# pcm2705_DAC.net
KiCad netlist of a schematic drawn in EAGLE
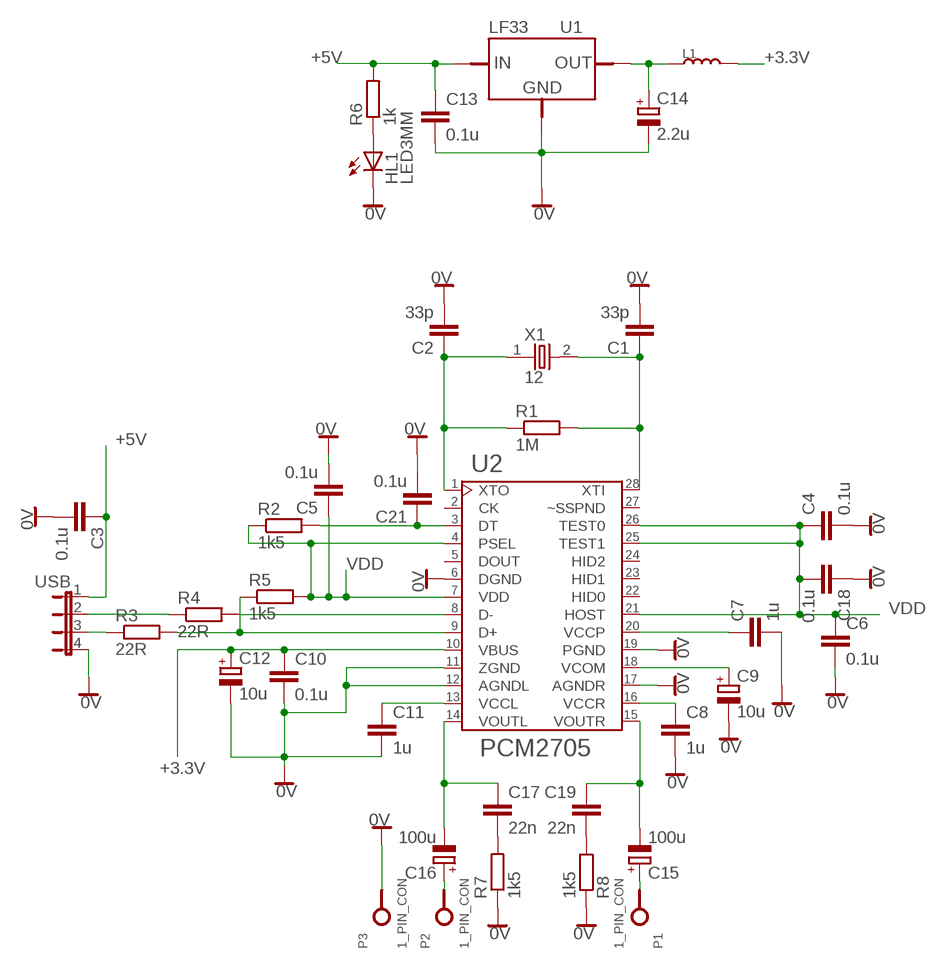
[diagram p0: schematic, sheet 1]

(export (version "E")
  (design (tool "Eeschema 10.0.6"))
  (components
    (comp (ref "C1")
      (value "33p")
      (footprint "eagle-import:C0805D")
      (libsource (lib "eagle-import") (part "C0805"))
    )
    (comp (ref "C2")
      (value "33p")
      (footprint "eagle-import:C0805D")
      (libsource (lib "eagle-import") (part "C0805"))
    )
    (comp (ref "C3")
      (value "0.1u")
      (footprint "eagle-import:C0805D")
      (libsource (lib "eagle-import") (part "C0805"))
    )
    (comp (ref "C4")
      (value "0.1u")
      (footprint "eagle-import:C0805D")
      (libsource (lib "eagle-import") (part "C0805"))
    )
    (comp (ref "C5")
      (value "0.1u")
      (footprint "eagle-import:C0805D")
      (libsource (lib "eagle-import") (part "C0805"))
    )
    (comp (ref "C6")
      (value "0.1u")
      (footprint "eagle-import:C0805D")
      (libsource (lib "eagle-import") (part "C0805"))
    )
    (comp (ref "C7")
      (value "1u")
      (footprint "eagle-import:C0805D")
      (libsource (lib "eagle-import") (part "C0805"))
    )
    (comp (ref "C8")
      (value "1u")
      (footprint "eagle-import:C0805D")
      (libsource (lib "eagle-import") (part "C0805"))
    )
    (comp (ref "C9")
      (value "10u")
      (footprint "eagle-import:C100MILX6X12")
      (libsource (lib "eagle-import") (part "C100MFX25V"))
    )
    (comp (ref "C10")
      (value "0.1u")
      (footprint "eagle-import:C0805D")
      (libsource (lib "eagle-import") (part "C0805"))
    )
    (comp (ref "C11")
      (value "1u")
      (footprint "eagle-import:C0805D")
      (libsource (lib "eagle-import") (part "C0805"))
    )
    (comp (ref "C12")
      (value "10u")
      (footprint "eagle-import:C100MILX6X12")
      (libsource (lib "eagle-import") (part "C100MFX25V"))
    )
    (comp (ref "C13")
      (value "0.1u")
      (footprint "eagle-import:C0805D")
      (libsource (lib "eagle-import") (part "C0805"))
    )
    (comp (ref "C14")
      (value "2.2u")
      (footprint "eagle-import:C100MILX6X12")
      (libsource (lib "eagle-import") (part "C100MFX25V"))
    )
    (comp (ref "C15")
      (value "100u")
      (footprint "eagle-import:C100MILX6X12")
      (libsource (lib "eagle-import") (part "C100MFX25V"))
    )
    (comp (ref "C16")
      (value "100u")
      (footprint "eagle-import:C100MILX6X12")
      (libsource (lib "eagle-import") (part "C100MFX25V"))
    )
    (comp (ref "C17")
      (value "22n")
      (footprint "eagle-import:C0805D")
      (libsource (lib "eagle-import") (part "C0805"))
    )
    (comp (ref "C18")
      (value "0.1u")
      (footprint "eagle-import:C0805D")
      (libsource (lib "eagle-import") (part "C0805"))
    )
    (comp (ref "C19")
      (value "22n")
      (footprint "eagle-import:C0805D")
      (libsource (lib "eagle-import") (part "C0805"))
    )
    (comp (ref "C21")
      (value "0.1u")
      (footprint "eagle-import:C0805D")
      (libsource (lib "eagle-import") (part "C0805"))
    )
    (comp (ref "HL1")
      (value "LED3MM")
      (footprint "eagle-import:LED3MM")
      (libsource (lib "eagle-import") (part "LED3MM"))
    )
    (comp (ref "L1")
      (value "INDUCTOR")
      (footprint "eagle-import:INDUCTOR")
      (libsource (lib "eagle-import") (part "INDUCTOR"))
    )
    (comp (ref "P1")
      (value "1_PIN_CON")
      (footprint "eagle-import:1_PIN_CON")
      (libsource (lib "eagle-import") (part "1_PIN_CON"))
    )
    (comp (ref "P2")
      (value "1_PIN_CON")
      (footprint "eagle-import:1_PIN_CON")
      (libsource (lib "eagle-import") (part "1_PIN_CON"))
    )
    (comp (ref "P3")
      (value "1_PIN_CON")
      (footprint "eagle-import:1_PIN_CON")
      (libsource (lib "eagle-import") (part "1_PIN_CON"))
    )
    (comp (ref "R1")
      (value "1M")
      (footprint "eagle-import:R0805D")
      (libsource (lib "eagle-import") (part "R0805"))
    )
    (comp (ref "R2")
      (value "1k5")
      (footprint "eagle-import:R0805D")
      (libsource (lib "eagle-import") (part "R0805"))
    )
    (comp (ref "R3")
      (value "22R")
      (footprint "eagle-import:R0805D")
      (libsource (lib "eagle-import") (part "R0805"))
    )
    (comp (ref "R4")
      (value "22R")
      (footprint "eagle-import:R0805D")
      (libsource (lib "eagle-import") (part "R0805"))
    )
    (comp (ref "R5")
      (value "1k5")
      (footprint "eagle-import:R0805D")
      (libsource (lib "eagle-import") (part "R0805"))
    )
    (comp (ref "R6")
      (value "1k")
      (footprint "eagle-import:R0805D")
      (libsource (lib "eagle-import") (part "R0805"))
    )
    (comp (ref "R7")
      (value "1k5")
      (footprint "eagle-import:R0805D")
      (libsource (lib "eagle-import") (part "R0805"))
    )
    (comp (ref "R8")
      (value "1k5")
      (footprint "eagle-import:R0805D")
      (libsource (lib "eagle-import") (part "R0805"))
    )
    (comp (ref "U1")
      (value "LF33")
      (footprint "eagle-import:LF33_DPAK")
      (libsource (lib "eagle-import") (part "LF33"))
    )
    (comp (ref "U2")
      (value "PCM2705")
      (footprint "eagle-import:PCM2705-TSSOP28")
      (libsource (lib "eagle-import") (part "PCM2705"))
    )
    (comp (ref "USB")
      (value "JP4E")
      (footprint "eagle-import:JP4")
      (libsource (lib "eagle-import") (part "JP4E"))
    )
    (comp (ref "X1")
      (value "12")
      (footprint "eagle-import:HC49_S")
      (libsource (lib "eagle-import") (part "HC49/S"))
    )
  )
  (nets
    (net (code "1") (name "/+3.3V") (class "Default")
      (node (ref "C10") (pin "1") (pinfunction "1_1") (pintype "passive"))
      (node (ref "C12") (pin "PLUS") (pinfunction "+_PLUS") (pintype "passive"))
      (node (ref "L1") (pin "P$2") (pinfunction "P$2_P$2") (pintype "bidirectional"))
      (node (ref "U2") (pin "10") (pinfunction "VBUS_10") (pintype "bidirectional"))
    )
    (net (code "2") (name "/+5V") (class "Default")
      (node (ref "C13") (pin "1") (pinfunction "1_1") (pintype "passive"))
      (node (ref "C3") (pin "1") (pinfunction "1_1") (pintype "passive"))
      (node (ref "R6") (pin "P$2") (pinfunction "2_P$2") (pintype "passive"))
      (node (ref "U1") (pin "@IN1") (pinfunction "IN_@IN1") (pintype "bidirectional"))
      (node (ref "USB") (pin "1") (pinfunction "1_1") (pintype "passive"))
    )
    (net (code "3") (name "/VDD") (class "Default")
      (node (ref "C18") (pin "2") (pinfunction "2_2") (pintype "passive"))
      (node (ref "C4") (pin "1") (pinfunction "1_1") (pintype "passive"))
      (node (ref "C5") (pin "1") (pinfunction "1_1") (pintype "passive"))
      (node (ref "C6") (pin "1") (pinfunction "1_1") (pintype "passive"))
      (node (ref "R2") (pin "P$1") (pinfunction "1_P$1") (pintype "passive"))
      (node (ref "R5") (pin "P$2") (pinfunction "2_P$2") (pintype "passive"))
      (node (ref "U2") (pin "21") (pinfunction "HOST_21") (pintype "bidirectional"))
      (node (ref "U2") (pin "25") (pinfunction "TEST1_25") (pintype "bidirectional"))
      (node (ref "U2") (pin "26") (pinfunction "TEST0_26") (pintype "bidirectional"))
      (node (ref "U2") (pin "7") (pinfunction "VDD_7") (pintype "bidirectional"))
    )
    (net (code "4") (name "0V") (class "Default")
      (node (ref "C1") (pin "2") (pinfunction "2_2") (pintype "passive"))
      (node (ref "C10") (pin "2") (pinfunction "2_2") (pintype "passive"))
      (node (ref "C11") (pin "2") (pinfunction "2_2") (pintype "passive"))
      (node (ref "C12") (pin "MINUS") (pinfunction "-_MINUS") (pintype "passive"))
      (node (ref "C13") (pin "2") (pinfunction "2_2") (pintype "passive"))
      (node (ref "C14") (pin "MINUS") (pinfunction "-_MINUS") (pintype "passive"))
      (node (ref "C18") (pin "1") (pinfunction "1_1") (pintype "passive"))
      (node (ref "C2") (pin "2") (pinfunction "2_2") (pintype "passive"))
      (node (ref "C21") (pin "2") (pinfunction "2_2") (pintype "passive"))
      (node (ref "C3") (pin "2") (pinfunction "2_2") (pintype "passive"))
      (node (ref "C4") (pin "2") (pinfunction "2_2") (pintype "passive"))
      (node (ref "C5") (pin "2") (pinfunction "2_2") (pintype "passive"))
      (node (ref "C6") (pin "2") (pinfunction "2_2") (pintype "passive"))
      (node (ref "C7") (pin "2") (pinfunction "2_2") (pintype "passive"))
      (node (ref "C8") (pin "2") (pinfunction "2_2") (pintype "passive"))
      (node (ref "C9") (pin "MINUS") (pinfunction "-_MINUS") (pintype "passive"))
      (node (ref "HL1") (pin "K") (pinfunction "C_K") (pintype "passive"))
      (node (ref "P3") (pin "P$1") (pinfunction "P$1_P$1") (pintype "bidirectional"))
      (node (ref "R7") (pin "P$1") (pinfunction "1_P$1") (pintype "passive"))
      (node (ref "R8") (pin "P$1") (pinfunction "1_P$1") (pintype "passive"))
      (node (ref "U1") (pin "@GND1") (pinfunction "GND_@GND1") (pintype "bidirectional"))
      (node (ref "U2") (pin "11") (pinfunction "ZGND_11") (pintype "bidirectional"))
      (node (ref "U2") (pin "12") (pinfunction "AGNDL_12") (pintype "bidirectional"))
      (node (ref "U2") (pin "17") (pinfunction "AGNDR_17") (pintype "bidirectional"))
      (node (ref "U2") (pin "19") (pinfunction "PGND_19") (pintype "bidirectional"))
      (node (ref "U2") (pin "6") (pinfunction "DGND_6") (pintype "bidirectional"))
      (node (ref "USB") (pin "4") (pinfunction "4_4") (pintype "passive"))
    )
    (net (code "5") (name "Net-(C9-+)") (class "Default")
      (node (ref "C9") (pin "PLUS") (pinfunction "+_PLUS") (pintype "passive"))
      (node (ref "U2") (pin "18") (pinfunction "VCOM_18") (pintype "bidirectional"))
    )
    (net (code "6") (name "Net-(C14-+)") (class "Default")
      (node (ref "C14") (pin "PLUS") (pinfunction "+_PLUS") (pintype "passive"))
      (node (ref "L1") (pin "P$1") (pinfunction "P$1_P$1") (pintype "bidirectional"))
      (node (ref "U1") (pin "@OUT1") (pinfunction "OUT_@OUT1") (pintype "bidirectional"))
    )
    (net (code "7") (name "Net-(C15-+)") (class "Default")
      (node (ref "C15") (pin "PLUS") (pinfunction "+_PLUS") (pintype "passive"))
      (node (ref "P1") (pin "P$1") (pinfunction "P$1_P$1") (pintype "bidirectional"))
    )
    (net (code "8") (name "Net-(C15--)") (class "Default")
      (node (ref "C15") (pin "MINUS") (pinfunction "-_MINUS") (pintype "passive"))
      (node (ref "C19") (pin "1") (pinfunction "1_1") (pintype "passive"))
      (node (ref "U2") (pin "15") (pinfunction "VOUTR_15") (pintype "bidirectional"))
    )
    (net (code "9") (name "Net-(C16-+)") (class "Default")
      (node (ref "C16") (pin "PLUS") (pinfunction "+_PLUS") (pintype "passive"))
      (node (ref "P2") (pin "P$1") (pinfunction "P$1_P$1") (pintype "bidirectional"))
    )
    (net (code "10") (name "Net-(C16--)") (class "Default")
      (node (ref "C16") (pin "MINUS") (pinfunction "-_MINUS") (pintype "passive"))
      (node (ref "C17") (pin "1") (pinfunction "1_1") (pintype "passive"))
      (node (ref "U2") (pin "14") (pinfunction "VOUTL_14") (pintype "bidirectional"))
    )
    (net (code "11") (name "Net-(R1-1)") (class "Default")
      (node (ref "C2") (pin "1") (pinfunction "1_1") (pintype "passive"))
      (node (ref "R1") (pin "P$1") (pinfunction "1_P$1") (pintype "passive"))
      (node (ref "U2") (pin "1") (pinfunction "XTO_1") (pintype "bidirectional"))
      (node (ref "X1") (pin "1") (pinfunction "1_1") (pintype "passive"))
    )
    (net (code "12") (name "Net-(R1-2)") (class "Default")
      (node (ref "C1") (pin "1") (pinfunction "1_1") (pintype "passive"))
      (node (ref "R1") (pin "P$2") (pinfunction "2_P$2") (pintype "passive"))
      (node (ref "U2") (pin "28") (pinfunction "XTI_28") (pintype "bidirectional"))
      (node (ref "X1") (pin "2") (pinfunction "2_2") (pintype "passive"))
    )
    (net (code "13") (name "Net-(R2-2)") (class "Default")
      (node (ref "C21") (pin "1") (pinfunction "1_1") (pintype "passive"))
      (node (ref "R2") (pin "P$2") (pinfunction "2_P$2") (pintype "passive"))
      (node (ref "U2") (pin "3") (pinfunction "DT_3") (pintype "bidirectional"))
    )
    (net (code "14") (name "Net-(R3-1)") (class "Default")
      (node (ref "R3") (pin "P$1") (pinfunction "1_P$1") (pintype "passive"))
      (node (ref "USB") (pin "3") (pinfunction "3_3") (pintype "passive"))
    )
    (net (code "15") (name "Net-(R3-2)") (class "Default")
      (node (ref "R3") (pin "P$2") (pinfunction "2_P$2") (pintype "passive"))
      (node (ref "R5") (pin "P$1") (pinfunction "1_P$1") (pintype "passive"))
      (node (ref "U2") (pin "9") (pinfunction "D+_9") (pintype "bidirectional"))
    )
    (net (code "16") (name "Net-(R4-1)") (class "Default")
      (node (ref "R4") (pin "P$1") (pinfunction "1_P$1") (pintype "passive"))
      (node (ref "USB") (pin "2") (pinfunction "2_2") (pintype "passive"))
    )
    (net (code "17") (name "Net-(R4-2)") (class "Default")
      (node (ref "R4") (pin "P$2") (pinfunction "2_P$2") (pintype "passive"))
      (node (ref "U2") (pin "8") (pinfunction "D-_8") (pintype "bidirectional"))
    )
    (net (code "18") (name "Net-(R6-1)") (class "Default")
      (node (ref "HL1") (pin "A") (pinfunction "A_A") (pintype "passive"))
      (node (ref "R6") (pin "P$1") (pinfunction "1_P$1") (pintype "passive"))
    )
    (net (code "19") (name "Net-(R7-2)") (class "Default")
      (node (ref "C17") (pin "2") (pinfunction "2_2") (pintype "passive"))
      (node (ref "R7") (pin "P$2") (pinfunction "2_P$2") (pintype "passive"))
    )
    (net (code "20") (name "Net-(R8-2)") (class "Default")
      (node (ref "C19") (pin "2") (pinfunction "2_2") (pintype "passive"))
      (node (ref "R8") (pin "P$2") (pinfunction "2_P$2") (pintype "passive"))
    )
    (net (code "21") (name "Net-(U2-VCCL)") (class "Default")
      (node (ref "C11") (pin "1") (pinfunction "1_1") (pintype "passive"))
      (node (ref "U2") (pin "13") (pinfunction "VCCL_13") (pintype "bidirectional"))
    )
    (net (code "22") (name "Net-(U2-VCCP)") (class "Default")
      (node (ref "C7") (pin "1") (pinfunction "1_1") (pintype "passive"))
      (node (ref "U2") (pin "20") (pinfunction "VCCP_20") (pintype "bidirectional"))
    )
    (net (code "23") (name "Net-(U2-VCCR)") (class "Default")
      (node (ref "C8") (pin "1") (pinfunction "1_1") (pintype "passive"))
      (node (ref "U2") (pin "16") (pinfunction "VCCR_16") (pintype "bidirectional"))
    )
    (net (code "24") (name "unconnected-(U2-CK-Pad2)") (class "Default")
      (node (ref "U2") (pin "2") (pinfunction "CK_2") (pintype "bidirectional"))
    )
    (net (code "25") (name "unconnected-(U2-DOUT-Pad5)") (class "Default")
      (node (ref "U2") (pin "5") (pinfunction "DOUT_5") (pintype "bidirectional"))
    )
    (net (code "26") (name "unconnected-(U2-HID0-Pad22)") (class "Default")
      (node (ref "U2") (pin "22") (pinfunction "HID0_22") (pintype "bidirectional"))
    )
    (net (code "27") (name "unconnected-(U2-HID1-Pad23)") (class "Default")
      (node (ref "U2") (pin "23") (pinfunction "HID1_23") (pintype "bidirectional"))
    )
    (net (code "28") (name "unconnected-(U2-HID2-Pad24)") (class "Default")
      (node (ref "U2") (pin "24") (pinfunction "HID2_24") (pintype "bidirectional"))
    )
    (net (code "29") (name "unconnected-(U2-PSEL-Pad4)") (class "Default")
      (node (ref "U2") (pin "4") (pinfunction "PSEL_4") (pintype "bidirectional"))
    )
    (net (code "30") (name "unconnected-(U2-~{SSPND}-Pad27)") (class "Default")
      (node (ref "U2") (pin "27") (pinfunction "~{SSPND}_27") (pintype "bidirectional"))
    )
  )
)
